# 8884bt_Remote_Control_Receiver.net
KiCad netlist of a schematic drawn in EAGLE
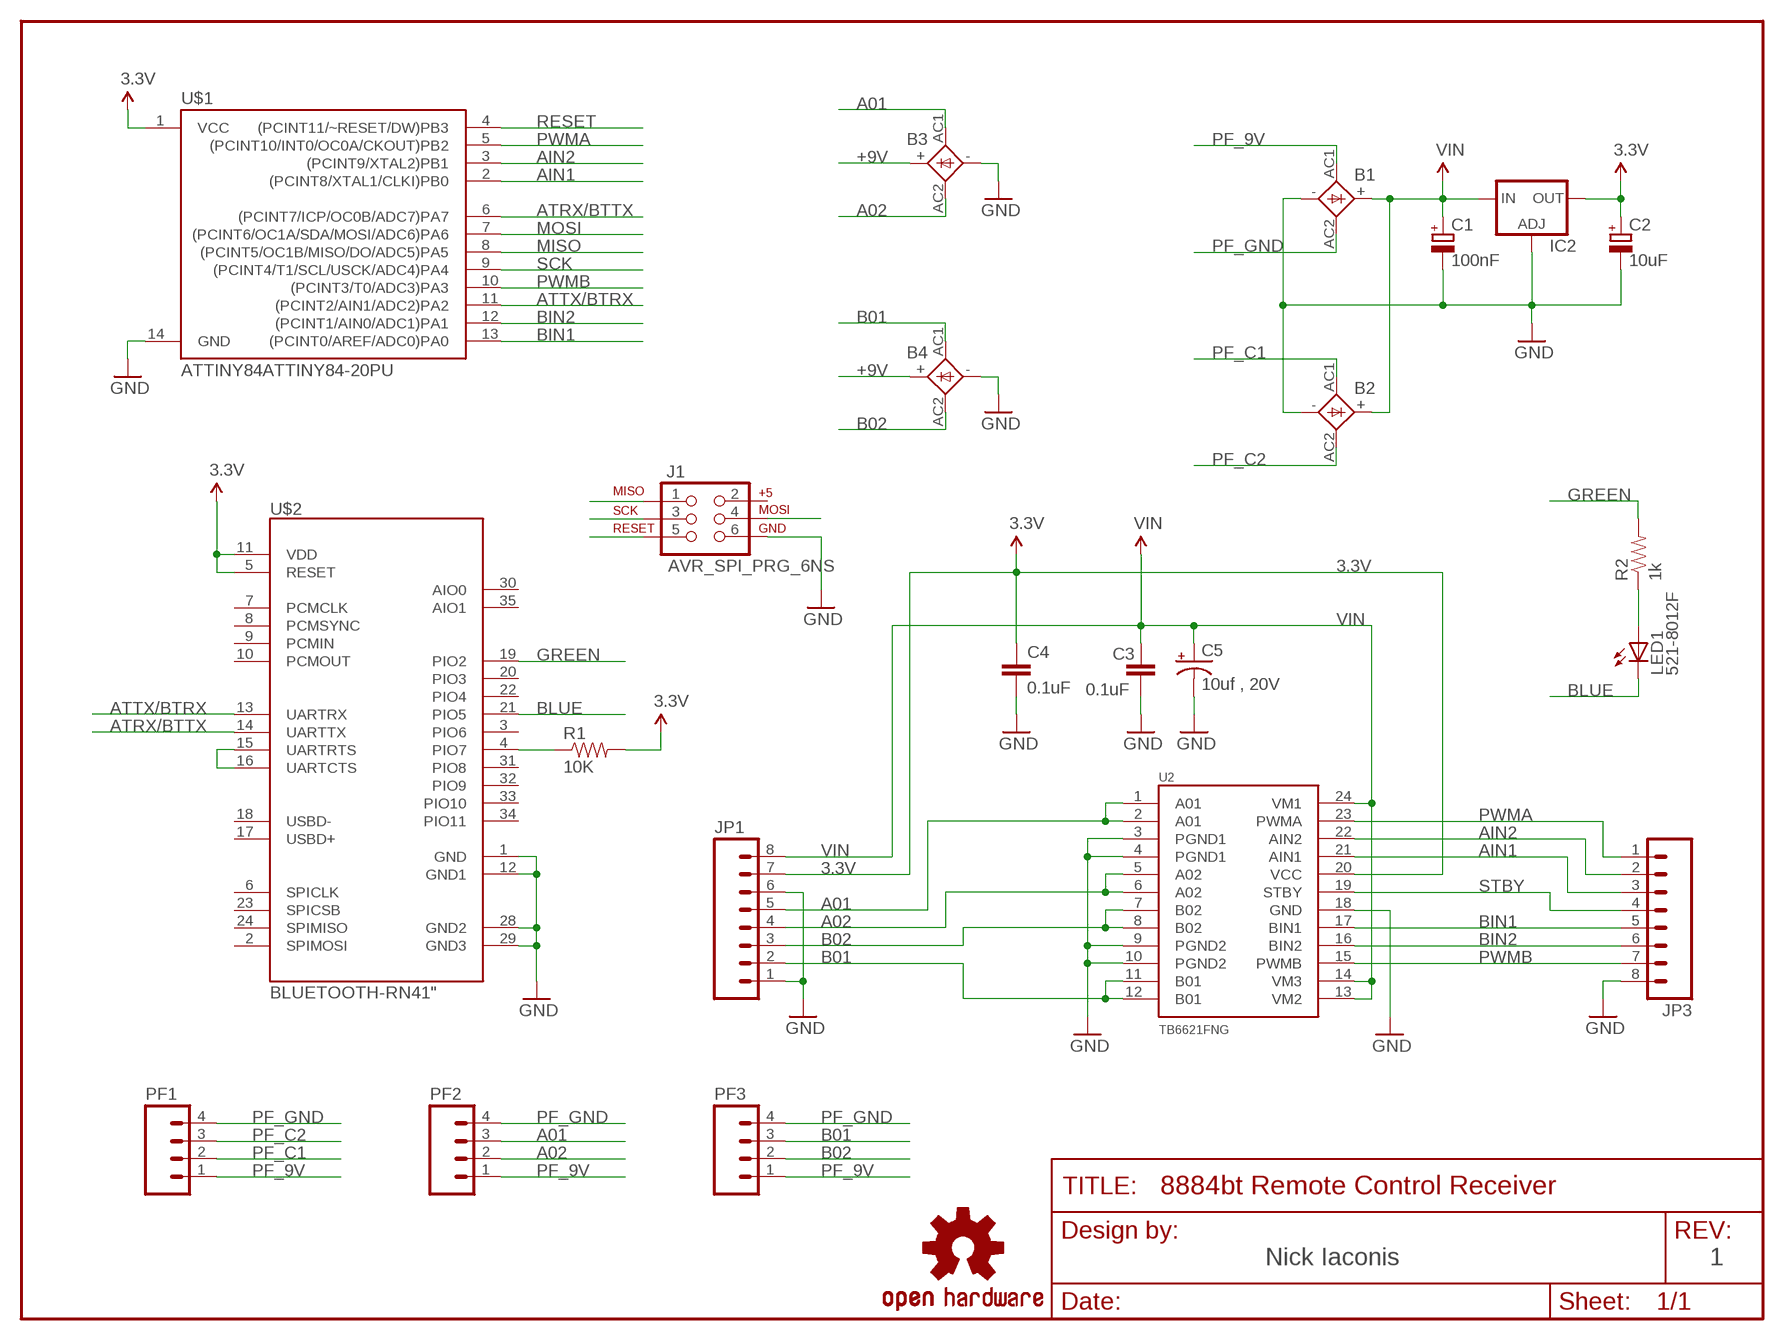
[diagram p0: schematic, sheet 1]

(export (version "E")
  (design (tool "Eeschema 10.0.6"))
  (components
    (comp (ref "B1")
      (value "2KBB-R")
      (footprint "eagle-import:2KBB-R")
      (libsource (lib "eagle-import") (part "2KBB-R"))
    )
    (comp (ref "B2")
      (value "2KBB-R")
      (footprint "eagle-import:2KBB-R")
      (libsource (lib "eagle-import") (part "2KBB-R"))
    )
    (comp (ref "B3")
      (value "2KBB-R")
      (footprint "eagle-import:2KBB-R")
      (libsource (lib "eagle-import") (part "2KBB-R"))
    )
    (comp (ref "B4")
      (value "2KBB-R")
      (footprint "eagle-import:2KBB-R")
      (libsource (lib "eagle-import") (part "2KBB-R"))
    )
    (comp (ref "C1")
      (value "100nF")
      (footprint "eagle-import:EB20D")
      (libsource (lib "eagle-import") (part "CPOL-EUE10-20"))
    )
    (comp (ref "C2")
      (value "10uF")
      (footprint "eagle-import:EB20D")
      (libsource (lib "eagle-import") (part "CPOL-EUE10-20"))
    )
    (comp (ref "C3")
      (value "0.1uF")
      (footprint "eagle-import:0402-CAP")
      (libsource (lib "eagle-import") (part "CAP0402-CAP"))
    )
    (comp (ref "C4")
      (value "0.1uF")
      (footprint "eagle-import:0402-CAP")
      (libsource (lib "eagle-import") (part "CAP0402-CAP"))
    )
    (comp (ref "C5")
      (value "10uf , 20V")
      (footprint "eagle-import:EIA3528")
      (libsource (lib "eagle-import") (part "CAP_POL3528"))
    )
    (comp (ref "IC2")
      (value "LM317TS")
      (footprint "eagle-import:317TS")
      (libsource (lib "eagle-import") (part "LM317TS"))
    )
    (comp (ref "J1")
      (value "AVR_SPI_PRG_6NS")
      (footprint "eagle-import:2X3-NS")
      (libsource (lib "eagle-import") (part "AVR_SPI_PRG_6NS"))
    )
    (comp (ref "JP1")
      (value "M08LONGPADS")
      (footprint "eagle-import:1X08_LONGPADS")
      (libsource (lib "eagle-import") (part "M08LONGPADS"))
    )
    (comp (ref "JP3")
      (value "M08LONGPADS")
      (footprint "eagle-import:1X08_LONGPADS")
      (libsource (lib "eagle-import") (part "M08LONGPADS"))
    )
    (comp (ref "LED1")
      (value "521-8012F")
      (footprint "eagle-import:LED3MM")
      (libsource (lib "eagle-import") (part "LED3MM"))
    )
    (comp (ref "LOGO1")
      (value "OSHW-LOGOM")
      (footprint "eagle-import:OSHW-LOGO-M")
      (libsource (lib "eagle-import") (part "OSHW-LOGOM"))
    )
    (comp (ref "PF1")
      (value "M04PTH")
      (footprint "eagle-import:1X04")
      (libsource (lib "eagle-import") (part "M04PTH"))
    )
    (comp (ref "PF2")
      (value "M04PTH")
      (footprint "eagle-import:1X04")
      (libsource (lib "eagle-import") (part "M04PTH"))
    )
    (comp (ref "PF3")
      (value "M04PTH")
      (footprint "eagle-import:1X04")
      (libsource (lib "eagle-import") (part "M04PTH"))
    )
    (comp (ref "R1")
      (value "10K")
      (footprint "eagle-import:0603-RES")
      (libsource (lib "eagle-import") (part "10KOHM1/10W1%(0603)0603"))
    )
    (comp (ref "R2")
      (value "1k")
      (footprint "eagle-import:0805")
      (libsource (lib "eagle-import") (part "RESISTOR0805-RES"))
    )
    (comp (ref "U$1")
      (value "ATTINY84ATTINY84-20PU")
      (footprint "eagle-import:DIL14")
      (libsource (lib "eagle-import") (part "ATTINY84ATTINY84-20PU"))
    )
    (comp (ref "U$2")
      (value "BLUETOOTH-RN41\"")
      (footprint "eagle-import:RN41")
      (libsource (lib "eagle-import") (part "BLUETOOTH-RN41{dblquote}"))
    )
    (comp (ref "U2")
      (value "TB6621FNG")
      (footprint "eagle-import:SSOP24")
      (libsource (lib "eagle-import") (part "TB6621FNG"))
    )
  )
  (nets
    (net (code "1") (name "/+9V") (class "Default")
      (node (ref "B3") (pin "+") (pinfunction "+_+") (pintype "passive"))
      (node (ref "B4") (pin "+") (pinfunction "+_+") (pintype "passive"))
    )
    (net (code "2") (name "/A01") (class "Default")
      (node (ref "B3") (pin "AC1") (pinfunction "AC1_AC1") (pintype "passive"))
      (node (ref "JP1") (pin "5") (pinfunction "5_5") (pintype "passive"))
      (node (ref "PF2") (pin "3") (pinfunction "3_3") (pintype "passive"))
      (node (ref "U2") (pin "1") (pinfunction "A01_1") (pintype "bidirectional"))
      (node (ref "U2") (pin "2") (pinfunction "A01_2") (pintype "bidirectional"))
    )
    (net (code "3") (name "/A02") (class "Default")
      (node (ref "B3") (pin "AC2") (pinfunction "AC2_AC2") (pintype "passive"))
      (node (ref "JP1") (pin "4") (pinfunction "4_4") (pintype "passive"))
      (node (ref "PF2") (pin "2") (pinfunction "2_2") (pintype "passive"))
      (node (ref "U2") (pin "5") (pinfunction "A02_5") (pintype "bidirectional"))
      (node (ref "U2") (pin "6") (pinfunction "A02_6") (pintype "bidirectional"))
    )
    (net (code "4") (name "/AIN1") (class "Default")
      (node (ref "JP3") (pin "3") (pinfunction "3_3") (pintype "passive"))
      (node (ref "U$1") (pin "2") (pinfunction "(PCINT8/XTAL1/CLKI)PB0_2") (pintype "bidirectional"))
      (node (ref "U2") (pin "21") (pinfunction "AIN1_21") (pintype "bidirectional"))
    )
    (net (code "5") (name "/AIN2") (class "Default")
      (node (ref "JP3") (pin "2") (pinfunction "2_2") (pintype "passive"))
      (node (ref "U$1") (pin "3") (pinfunction "(PCINT9/XTAL2)PB1_3") (pintype "bidirectional"))
      (node (ref "U2") (pin "22") (pinfunction "AIN2_22") (pintype "bidirectional"))
    )
    (net (code "6") (name "/ATRX{slash}BTTX") (class "Default")
      (node (ref "U$1") (pin "6") (pinfunction "(PCINT7/ICP/OC0B/ADC7)PA7_6") (pintype "bidirectional"))
      (node (ref "U$2") (pin "14") (pinfunction "UARTTX_14") (pintype "bidirectional"))
    )
    (net (code "7") (name "/ATTX{slash}BTRX") (class "Default")
      (node (ref "U$1") (pin "11") (pinfunction "(PCINT2/AIN1/ADC2)PA2_11") (pintype "bidirectional"))
      (node (ref "U$2") (pin "13") (pinfunction "UARTRX_13") (pintype "bidirectional"))
    )
    (net (code "8") (name "/B01") (class "Default")
      (node (ref "B4") (pin "AC1") (pinfunction "AC1_AC1") (pintype "passive"))
      (node (ref "JP1") (pin "2") (pinfunction "2_2") (pintype "passive"))
      (node (ref "PF3") (pin "3") (pinfunction "3_3") (pintype "passive"))
      (node (ref "U2") (pin "11") (pinfunction "B01_11") (pintype "bidirectional"))
      (node (ref "U2") (pin "12") (pinfunction "B01_12") (pintype "bidirectional"))
    )
    (net (code "9") (name "/B02") (class "Default")
      (node (ref "B4") (pin "AC2") (pinfunction "AC2_AC2") (pintype "passive"))
      (node (ref "JP1") (pin "3") (pinfunction "3_3") (pintype "passive"))
      (node (ref "PF3") (pin "2") (pinfunction "2_2") (pintype "passive"))
      (node (ref "U2") (pin "7") (pinfunction "B02_7") (pintype "bidirectional"))
      (node (ref "U2") (pin "8") (pinfunction "B02_8") (pintype "bidirectional"))
    )
    (net (code "10") (name "/BIN1") (class "Default")
      (node (ref "JP3") (pin "5") (pinfunction "5_5") (pintype "passive"))
      (node (ref "U$1") (pin "13") (pinfunction "(PCINT0/AREF/ADC0)PA0_13") (pintype "bidirectional"))
      (node (ref "U2") (pin "17") (pinfunction "BIN1_17") (pintype "bidirectional"))
    )
    (net (code "11") (name "/BIN2") (class "Default")
      (node (ref "JP3") (pin "6") (pinfunction "6_6") (pintype "passive"))
      (node (ref "U$1") (pin "12") (pinfunction "(PCINT1/AIN0/ADC1)PA1_12") (pintype "bidirectional"))
      (node (ref "U2") (pin "16") (pinfunction "BIN2_16") (pintype "bidirectional"))
    )
    (net (code "12") (name "/BLUE") (class "Default")
      (node (ref "LED1") (pin "K") (pinfunction "C_K") (pintype "passive"))
      (node (ref "U$2") (pin "21") (pinfunction "PIO5_21") (pintype "bidirectional"))
    )
    (net (code "13") (name "/GREEN") (class "Default")
      (node (ref "R2") (pin "2") (pinfunction "2_2") (pintype "passive"))
      (node (ref "U$2") (pin "19") (pinfunction "PIO2_19") (pintype "bidirectional"))
    )
    (net (code "14") (name "/MISO") (class "Default")
      (node (ref "J1") (pin "1") (pinfunction "1_1") (pintype "passive"))
      (node (ref "U$1") (pin "8") (pinfunction "(PCINT5/OC1B/MISO/DO/ADC5)PA5_8") (pintype "bidirectional"))
    )
    (net (code "15") (name "/MOSI") (class "Default")
      (node (ref "J1") (pin "4") (pinfunction "4_4") (pintype "passive"))
      (node (ref "U$1") (pin "7") (pinfunction "(PCINT6/OC1A/SDA/MOSI/ADC6)PA6_7") (pintype "bidirectional"))
    )
    (net (code "16") (name "/PF_9V") (class "Default")
      (node (ref "B1") (pin "AC1") (pinfunction "AC1_AC1") (pintype "passive"))
      (node (ref "PF1") (pin "1") (pinfunction "1_1") (pintype "passive"))
      (node (ref "PF2") (pin "1") (pinfunction "1_1") (pintype "passive"))
      (node (ref "PF3") (pin "1") (pinfunction "1_1") (pintype "passive"))
    )
    (net (code "17") (name "/PF_C1") (class "Default")
      (node (ref "B2") (pin "AC1") (pinfunction "AC1_AC1") (pintype "passive"))
      (node (ref "PF1") (pin "2") (pinfunction "2_2") (pintype "passive"))
    )
    (net (code "18") (name "/PF_C2") (class "Default")
      (node (ref "B2") (pin "AC2") (pinfunction "AC2_AC2") (pintype "passive"))
      (node (ref "PF1") (pin "3") (pinfunction "3_3") (pintype "passive"))
    )
    (net (code "19") (name "/PF_GND") (class "Default")
      (node (ref "B1") (pin "AC2") (pinfunction "AC2_AC2") (pintype "passive"))
      (node (ref "PF1") (pin "4") (pinfunction "4_4") (pintype "passive"))
      (node (ref "PF2") (pin "4") (pinfunction "4_4") (pintype "passive"))
      (node (ref "PF3") (pin "4") (pinfunction "4_4") (pintype "passive"))
    )
    (net (code "20") (name "/PWMA") (class "Default")
      (node (ref "JP3") (pin "1") (pinfunction "1_1") (pintype "passive"))
      (node (ref "U$1") (pin "5") (pinfunction "(PCINT10/INT0/OC0A/CKOUT)PB2_5") (pintype "bidirectional"))
      (node (ref "U2") (pin "23") (pinfunction "PWMA_23") (pintype "bidirectional"))
    )
    (net (code "21") (name "/PWMB") (class "Default")
      (node (ref "JP3") (pin "7") (pinfunction "7_7") (pintype "passive"))
      (node (ref "U$1") (pin "10") (pinfunction "(PCINT3/T0/ADC3)PA3_10") (pintype "bidirectional"))
      (node (ref "U2") (pin "15") (pinfunction "PWMB_15") (pintype "bidirectional"))
    )
    (net (code "22") (name "/RESET") (class "Default")
      (node (ref "J1") (pin "5") (pinfunction "5_5") (pintype "passive"))
      (node (ref "U$1") (pin "4") (pinfunction "(PCINT11/~{RESET/DW})PB3_4") (pintype "bidirectional"))
    )
    (net (code "23") (name "/SCK") (class "Default")
      (node (ref "J1") (pin "3") (pinfunction "3_3") (pintype "passive"))
      (node (ref "U$1") (pin "9") (pinfunction "(PCINT4/T1/SCL/USCK/ADC4)PA4_9") (pintype "bidirectional"))
    )
    (net (code "24") (name "/STBY") (class "Default")
      (node (ref "JP3") (pin "4") (pinfunction "4_4") (pintype "passive"))
      (node (ref "U2") (pin "19") (pinfunction "STBY_19") (pintype "bidirectional"))
    )
    (net (code "25") (name "3.3V") (class "Default")
      (node (ref "C2") (pin "+") (pinfunction "+_+") (pintype "passive"))
      (node (ref "C4") (pin "1") (pinfunction "1_1") (pintype "passive"))
      (node (ref "IC2") (pin "2") (pinfunction "OUT_2") (pintype "passive"))
      (node (ref "JP1") (pin "7") (pinfunction "7_7") (pintype "passive"))
      (node (ref "R1") (pin "2") (pinfunction "2_2") (pintype "passive"))
      (node (ref "U$1") (pin "1") (pinfunction "VCC_1") (pintype "bidirectional"))
      (node (ref "U$2") (pin "11") (pinfunction "VDD_11") (pintype "bidirectional"))
      (node (ref "U$2") (pin "5") (pinfunction "RESET_5") (pintype "bidirectional"))
      (node (ref "U2") (pin "20") (pinfunction "VCC_20") (pintype "bidirectional"))
    )
    (net (code "26") (name "GND") (class "Default")
      (node (ref "B1") (pin "-") (pinfunction "-_-") (pintype "passive"))
      (node (ref "B2") (pin "-") (pinfunction "-_-") (pintype "passive"))
      (node (ref "B3") (pin "-") (pinfunction "-_-") (pintype "passive"))
      (node (ref "B4") (pin "-") (pinfunction "-_-") (pintype "passive"))
      (node (ref "C1") (pin "-") (pinfunction "-_-") (pintype "passive"))
      (node (ref "C2") (pin "-") (pinfunction "-_-") (pintype "passive"))
      (node (ref "C3") (pin "2") (pinfunction "2_2") (pintype "passive"))
      (node (ref "C4") (pin "2") (pinfunction "2_2") (pintype "passive"))
      (node (ref "C5") (pin "C") (pinfunction "-_C") (pintype "passive"))
      (node (ref "IC2") (pin "1") (pinfunction "ADJ_1") (pintype "input"))
      (node (ref "J1") (pin "6") (pinfunction "6_6") (pintype "passive"))
      (node (ref "JP1") (pin "1") (pinfunction "1_1") (pintype "passive"))
      (node (ref "JP1") (pin "6") (pinfunction "6_6") (pintype "passive"))
      (node (ref "JP3") (pin "8") (pinfunction "8_8") (pintype "passive"))
      (node (ref "U$1") (pin "14") (pinfunction "GND_14") (pintype "bidirectional"))
      (node (ref "U$2") (pin "1") (pinfunction "GND_1") (pintype "bidirectional"))
      (node (ref "U$2") (pin "12") (pinfunction "GND1_12") (pintype "bidirectional"))
      (node (ref "U$2") (pin "28") (pinfunction "GND2_28") (pintype "bidirectional"))
      (node (ref "U$2") (pin "29") (pinfunction "GND3_29") (pintype "bidirectional"))
      (node (ref "U2") (pin "10") (pinfunction "PGND2_10") (pintype "bidirectional"))
      (node (ref "U2") (pin "18") (pinfunction "GND_18") (pintype "bidirectional"))
      (node (ref "U2") (pin "3") (pinfunction "PGND1_3") (pintype "bidirectional"))
      (node (ref "U2") (pin "4") (pinfunction "PGND1_4") (pintype "bidirectional"))
      (node (ref "U2") (pin "9") (pinfunction "PGND2_9") (pintype "bidirectional"))
    )
    (net (code "27") (name "Net-(LED1-PadA)") (class "Default")
      (node (ref "LED1") (pin "A") (pinfunction "A_A") (pintype "passive"))
      (node (ref "R2") (pin "1") (pinfunction "1_1") (pintype "passive"))
    )
    (net (code "28") (name "Net-(U$2-PIO7)") (class "Default")
      (node (ref "R1") (pin "1") (pinfunction "1_1") (pintype "passive"))
      (node (ref "U$2") (pin "4") (pinfunction "PIO7_4") (pintype "bidirectional"))
    )
    (net (code "29") (name "Net-(U$2-UARTCTS)") (class "Default")
      (node (ref "U$2") (pin "15") (pinfunction "UARTRTS_15") (pintype "bidirectional"))
      (node (ref "U$2") (pin "16") (pinfunction "UARTCTS_16") (pintype "bidirectional"))
    )
    (net (code "30") (name "VIN") (class "Default")
      (node (ref "B1") (pin "+") (pinfunction "+_+") (pintype "passive"))
      (node (ref "B2") (pin "+") (pinfunction "+_+") (pintype "passive"))
      (node (ref "C1") (pin "+") (pinfunction "+_+") (pintype "passive"))
      (node (ref "C3") (pin "1") (pinfunction "1_1") (pintype "passive"))
      (node (ref "C5") (pin "A") (pinfunction "+_A") (pintype "passive"))
      (node (ref "IC2") (pin "3") (pinfunction "IN_3") (pintype "input"))
      (node (ref "JP1") (pin "8") (pinfunction "8_8") (pintype "passive"))
      (node (ref "U2") (pin "13") (pinfunction "VM2_13") (pintype "bidirectional"))
      (node (ref "U2") (pin "14") (pinfunction "VM3_14") (pintype "bidirectional"))
      (node (ref "U2") (pin "24") (pinfunction "VM1_24") (pintype "bidirectional"))
    )
    (net (code "31") (name "unconnected-(J1-Pad2)") (class "Default")
      (node (ref "J1") (pin "2") (pinfunction "2_2") (pintype "passive"))
    )
    (net (code "32") (name "unconnected-(U$2-AIO0-Pad30)") (class "Default")
      (node (ref "U$2") (pin "30") (pinfunction "AIO0_30") (pintype "bidirectional"))
    )
    (net (code "33") (name "unconnected-(U$2-AIO1-Pad35)") (class "Default")
      (node (ref "U$2") (pin "35") (pinfunction "AIO1_35") (pintype "bidirectional"))
    )
    (net (code "34") (name "unconnected-(U$2-PCMCLK-Pad7)") (class "Default")
      (node (ref "U$2") (pin "7") (pinfunction "PCMCLK_7") (pintype "bidirectional"))
    )
    (net (code "35") (name "unconnected-(U$2-PCMIN-Pad9)") (class "Default")
      (node (ref "U$2") (pin "9") (pinfunction "PCMIN_9") (pintype "bidirectional"))
    )
    (net (code "36") (name "unconnected-(U$2-PCMOUT-Pad10)") (class "Default")
      (node (ref "U$2") (pin "10") (pinfunction "PCMOUT_10") (pintype "bidirectional"))
    )
    (net (code "37") (name "unconnected-(U$2-PCMSYNC-Pad8)") (class "Default")
      (node (ref "U$2") (pin "8") (pinfunction "PCMSYNC_8") (pintype "bidirectional"))
    )
    (net (code "38") (name "unconnected-(U$2-PIO3-Pad20)") (class "Default")
      (node (ref "U$2") (pin "20") (pinfunction "PIO3_20") (pintype "bidirectional"))
    )
    (net (code "39") (name "unconnected-(U$2-PIO4-Pad22)") (class "Default")
      (node (ref "U$2") (pin "22") (pinfunction "PIO4_22") (pintype "bidirectional"))
    )
    (net (code "40") (name "unconnected-(U$2-PIO6-Pad3)") (class "Default")
      (node (ref "U$2") (pin "3") (pinfunction "PIO6_3") (pintype "bidirectional"))
    )
    (net (code "41") (name "unconnected-(U$2-PIO8-Pad31)") (class "Default")
      (node (ref "U$2") (pin "31") (pinfunction "PIO8_31") (pintype "bidirectional"))
    )
    (net (code "42") (name "unconnected-(U$2-PIO9-Pad32)") (class "Default")
      (node (ref "U$2") (pin "32") (pinfunction "PIO9_32") (pintype "bidirectional"))
    )
    (net (code "43") (name "unconnected-(U$2-PIO10-Pad33)") (class "Default")
      (node (ref "U$2") (pin "33") (pinfunction "PIO10_33") (pintype "bidirectional"))
    )
    (net (code "44") (name "unconnected-(U$2-PIO11-Pad34)") (class "Default")
      (node (ref "U$2") (pin "34") (pinfunction "PIO11_34") (pintype "bidirectional"))
    )
    (net (code "45") (name "unconnected-(U$2-SPICLK-Pad6)") (class "Default")
      (node (ref "U$2") (pin "6") (pinfunction "SPICLK_6") (pintype "bidirectional"))
    )
    (net (code "46") (name "unconnected-(U$2-SPICSB-Pad23)") (class "Default")
      (node (ref "U$2") (pin "23") (pinfunction "SPICSB_23") (pintype "bidirectional"))
    )
    (net (code "47") (name "unconnected-(U$2-SPIMISO-Pad24)") (class "Default")
      (node (ref "U$2") (pin "24") (pinfunction "SPIMISO_24") (pintype "bidirectional"))
    )
    (net (code "48") (name "unconnected-(U$2-SPIMOSI-Pad2)") (class "Default")
      (node (ref "U$2") (pin "2") (pinfunction "SPIMOSI_2") (pintype "bidirectional"))
    )
    (net (code "49") (name "unconnected-(U$2-USBD+-Pad17)") (class "Default")
      (node (ref "U$2") (pin "17") (pinfunction "USBD+_17") (pintype "bidirectional"))
    )
    (net (code "50") (name "unconnected-(U$2-USBD--Pad18)") (class "Default")
      (node (ref "U$2") (pin "18") (pinfunction "USBD-_18") (pintype "bidirectional"))
    )
  )
)
